# simduino.net
KiCad netlist of a schematic drawn in EAGLE
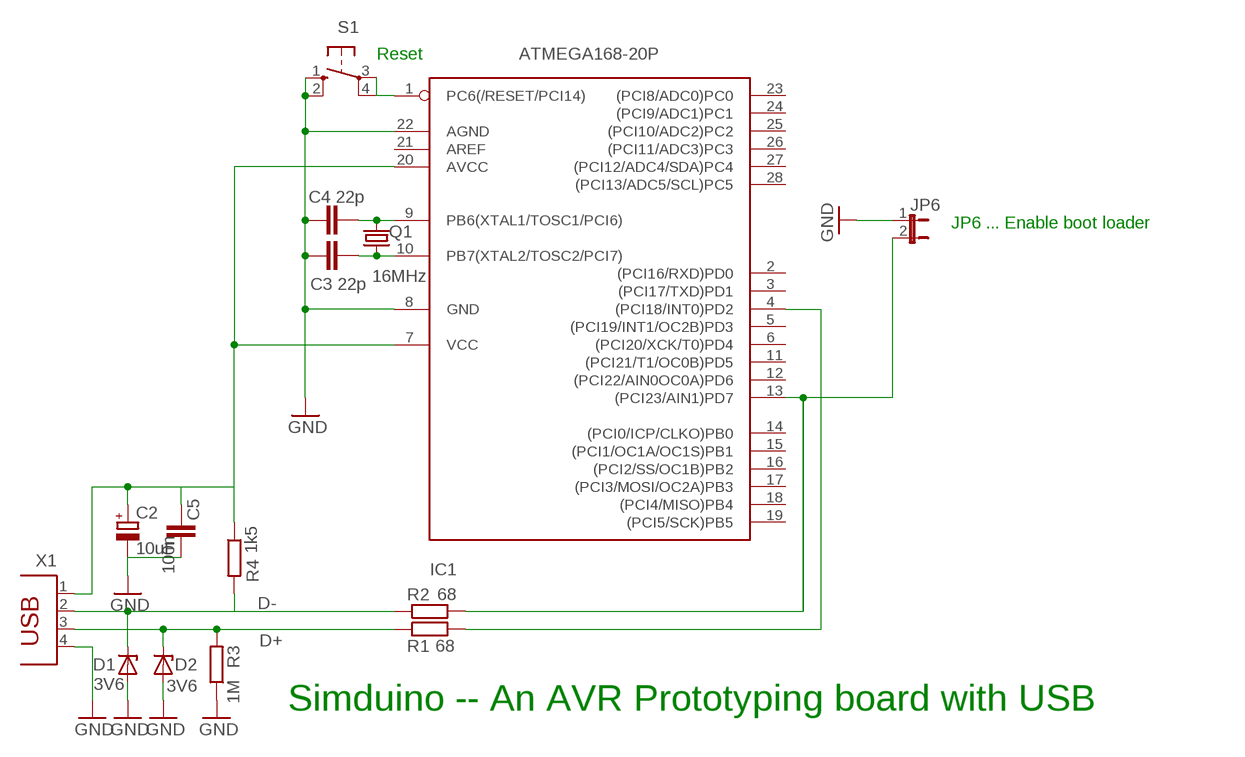
[diagram p0: schematic, sheet 1]

(export (version "E")
  (design (tool "Eeschema 10.0.6"))
  (components
    (comp (ref "C2")
      (value "10uF")
      (footprint "eagle-import:E2,5-6E")
      (libsource (lib "eagle-import") (part "CPOL-EUE2,5-6E"))
    )
    (comp (ref "C3")
      (value "22p")
      (footprint "eagle-import:C025-024X044")
      (libsource (lib "eagle-import") (part "C-EU025-024X044"))
    )
    (comp (ref "C4")
      (value "22p")
      (footprint "eagle-import:C025-024X044")
      (libsource (lib "eagle-import") (part "C-EU025-024X044"))
    )
    (comp (ref "C5")
      (value "100n")
      (footprint "eagle-import:C025_050-025X075")
      (libsource (lib "eagle-import") (part "C-EU025_050-025X075"))
    )
    (comp (ref "D1")
      (value "3V6")
      (footprint "eagle-import:DO34Z7")
      (libsource (lib "eagle-import") (part "ZENER-DIODEDO34-7"))
    )
    (comp (ref "D2")
      (value "3V6")
      (footprint "eagle-import:DO34Z7")
      (libsource (lib "eagle-import") (part "ZENER-DIODEDO34-7"))
    )
    (comp (ref "IC1")
      (value "ATMEGA168-20P")
      (footprint "eagle-import:DIL28-3")
      (libsource (lib "eagle-import") (part "ATMEGA168P-20"))
    )
    (comp (ref "JP6")
      (value "JP1E")
      (footprint "eagle-import:JP1")
      (libsource (lib "eagle-import") (part "JP1E"))
    )
    (comp (ref "Q1")
      (value "16MHz")
      (footprint "eagle-import:HC49_S")
      (libsource (lib "eagle-import") (part "CRYSTALHC49S"))
    )
    (comp (ref "R1")
      (value "68")
      (footprint "eagle-import:0207_10")
      (libsource (lib "eagle-import") (part "R-EU_0207/10"))
    )
    (comp (ref "R2")
      (value "68")
      (footprint "eagle-import:0207_10")
      (libsource (lib "eagle-import") (part "R-EU_0207/10"))
    )
    (comp (ref "R3")
      (value "1M")
      (footprint "eagle-import:0207_10")
      (libsource (lib "eagle-import") (part "R-EU_0207/10"))
    )
    (comp (ref "R4")
      (value "1k5")
      (footprint "eagle-import:0207_10")
      (libsource (lib "eagle-import") (part "R-EU_0207/10"))
    )
    (comp (ref "S1")
      (value "10-XX")
      (footprint "eagle-import:B3F-10XX")
      (libsource (lib "eagle-import") (part "10-XX"))
    )
    (comp (ref "X1")
      (value "PN61729")
      (footprint "eagle-import:PN61729")
      (libsource (lib "eagle-import") (part "PN61729"))
    )
  )
  (nets
    (net (code "1") (name "/D+") (class "Default")
      (node (ref "D2") (pin "C") (pinfunction "C_C") (pintype "passive"))
      (node (ref "R1") (pin "1") (pinfunction "1_1") (pintype "passive"))
      (node (ref "R3") (pin "2") (pinfunction "2_2") (pintype "passive"))
      (node (ref "X1") (pin "3") (pinfunction "3_3") (pintype "bidirectional"))
    )
    (net (code "2") (name "/D-") (class "Default")
      (node (ref "D1") (pin "C") (pinfunction "C_C") (pintype "passive"))
      (node (ref "R2") (pin "1") (pinfunction "1_1") (pintype "passive"))
      (node (ref "R4") (pin "2") (pinfunction "2_2") (pintype "passive"))
      (node (ref "X1") (pin "2") (pinfunction "2_2") (pintype "bidirectional"))
    )
    (net (code "3") (name "GND") (class "Default")
      (node (ref "C2") (pin "-") (pinfunction "-_-") (pintype "passive"))
      (node (ref "C3") (pin "1") (pinfunction "1_1") (pintype "passive"))
      (node (ref "C4") (pin "1") (pinfunction "1_1") (pintype "passive"))
      (node (ref "C5") (pin "2") (pinfunction "2_2") (pintype "passive"))
      (node (ref "D1") (pin "A") (pinfunction "A_A") (pintype "passive"))
      (node (ref "D2") (pin "A") (pinfunction "A_A") (pintype "passive"))
      (node (ref "IC1") (pin "22") (pinfunction "AGND_22") (pintype "bidirectional"))
      (node (ref "IC1") (pin "8") (pinfunction "GND_8") (pintype "bidirectional"))
      (node (ref "JP6") (pin "1") (pinfunction "1_1") (pintype "passive"))
      (node (ref "R3") (pin "1") (pinfunction "1_1") (pintype "passive"))
      (node (ref "S1") (pin "1") (pinfunction "S_1") (pintype "passive"))
      (node (ref "S1") (pin "2") (pinfunction "S1_2") (pintype "passive"))
      (node (ref "X1") (pin "4") (pinfunction "4_4") (pintype "bidirectional"))
    )
    (net (code "4") (name "Net-(IC1-(PCI18{slash}INT0)PD2)") (class "Default")
      (node (ref "IC1") (pin "4") (pinfunction "(PCI18/INT0)PD2_4") (pintype "bidirectional"))
      (node (ref "R1") (pin "2") (pinfunction "2_2") (pintype "passive"))
    )
    (net (code "5") (name "Net-(IC1-(PCI23{slash}AIN1)PD7)") (class "Default")
      (node (ref "IC1") (pin "13") (pinfunction "(PCI23/AIN1)PD7_13") (pintype "bidirectional"))
      (node (ref "JP6") (pin "2") (pinfunction "2_2") (pintype "passive"))
      (node (ref "R2") (pin "2") (pinfunction "2_2") (pintype "passive"))
    )
    (net (code "6") (name "Net-(IC1-AVCC)") (class "Default")
      (node (ref "C2") (pin "+") (pinfunction "+_+") (pintype "passive"))
      (node (ref "C5") (pin "1") (pinfunction "1_1") (pintype "passive"))
      (node (ref "IC1") (pin "20") (pinfunction "AVCC_20") (pintype "bidirectional"))
      (node (ref "IC1") (pin "7") (pinfunction "VCC_7") (pintype "bidirectional"))
      (node (ref "R4") (pin "1") (pinfunction "1_1") (pintype "passive"))
      (node (ref "X1") (pin "1") (pinfunction "1_1") (pintype "bidirectional"))
    )
    (net (code "7") (name "Net-(IC1-PB6(XTAL1{slash}TOSC1{slash}PCI6))") (class "Default")
      (node (ref "C4") (pin "2") (pinfunction "2_2") (pintype "passive"))
      (node (ref "IC1") (pin "9") (pinfunction "PB6(XTAL1/TOSC1/PCI6)_9") (pintype "bidirectional"))
      (node (ref "Q1") (pin "2") (pinfunction "2_2") (pintype "passive"))
    )
    (net (code "8") (name "Net-(IC1-PB7(XTAL2{slash}TOSC2{slash}PCI7))") (class "Default")
      (node (ref "C3") (pin "2") (pinfunction "2_2") (pintype "passive"))
      (node (ref "IC1") (pin "10") (pinfunction "PB7(XTAL2/TOSC2/PCI7)_10") (pintype "bidirectional"))
      (node (ref "Q1") (pin "1") (pinfunction "1_1") (pintype "passive"))
    )
    (net (code "9") (name "Net-(IC1-PC6({slash}RESET{slash}PCI14))") (class "Default")
      (node (ref "IC1") (pin "1") (pinfunction "PC6(/RESET/PCI14)_1") (pintype "bidirectional"))
      (node (ref "S1") (pin "3") (pinfunction "P_3") (pintype "passive"))
      (node (ref "S1") (pin "4") (pinfunction "P1_4") (pintype "passive"))
    )
    (net (code "10") (name "unconnected-(IC1-(PCI0{slash}ICP{slash}CLKO)PB0-Pad14)") (class "Default")
      (node (ref "IC1") (pin "14") (pinfunction "(PCI0/ICP/CLKO)PB0_14") (pintype "bidirectional"))
    )
    (net (code "11") (name "unconnected-(IC1-(PCI1{slash}OC1A{slash}OC1S)PB1-Pad15)") (class "Default")
      (node (ref "IC1") (pin "15") (pinfunction "(PCI1/OC1A/OC1S)PB1_15") (pintype "bidirectional"))
    )
    (net (code "12") (name "unconnected-(IC1-(PCI2{slash}SS{slash}OC1B)PB2-Pad16)") (class "Default")
      (node (ref "IC1") (pin "16") (pinfunction "(PCI2/SS/OC1B)PB2_16") (pintype "bidirectional"))
    )
    (net (code "13") (name "unconnected-(IC1-(PCI3{slash}MOSI{slash}OC2A)PB3-Pad17)") (class "Default")
      (node (ref "IC1") (pin "17") (pinfunction "(PCI3/MOSI/OC2A)PB3_17") (pintype "bidirectional"))
    )
    (net (code "14") (name "unconnected-(IC1-(PCI4{slash}MISO)PB4-Pad18)") (class "Default")
      (node (ref "IC1") (pin "18") (pinfunction "(PCI4/MISO)PB4_18") (pintype "bidirectional"))
    )
    (net (code "15") (name "unconnected-(IC1-(PCI5{slash}SCK)PB5-Pad19)") (class "Default")
      (node (ref "IC1") (pin "19") (pinfunction "(PCI5/SCK)PB5_19") (pintype "bidirectional"))
    )
    (net (code "16") (name "unconnected-(IC1-(PCI8{slash}ADC0)PC0-Pad23)") (class "Default")
      (node (ref "IC1") (pin "23") (pinfunction "(PCI8/ADC0)PC0_23") (pintype "bidirectional"))
    )
    (net (code "17") (name "unconnected-(IC1-(PCI9{slash}ADC1)PC1-Pad24)") (class "Default")
      (node (ref "IC1") (pin "24") (pinfunction "(PCI9/ADC1)PC1_24") (pintype "bidirectional"))
    )
    (net (code "18") (name "unconnected-(IC1-(PCI10{slash}ADC2)PC2-Pad25)") (class "Default")
      (node (ref "IC1") (pin "25") (pinfunction "(PCI10/ADC2)PC2_25") (pintype "bidirectional"))
    )
    (net (code "19") (name "unconnected-(IC1-(PCI11{slash}ADC3)PC3-Pad26)") (class "Default")
      (node (ref "IC1") (pin "26") (pinfunction "(PCI11/ADC3)PC3_26") (pintype "bidirectional"))
    )
    (net (code "20") (name "unconnected-(IC1-(PCI12{slash}ADC4{slash}SDA)PC4-Pad27)") (class "Default")
      (node (ref "IC1") (pin "27") (pinfunction "(PCI12/ADC4/SDA)PC4_27") (pintype "bidirectional"))
    )
    (net (code "21") (name "unconnected-(IC1-(PCI13{slash}ADC5{slash}SCL)PC5-Pad28)") (class "Default")
      (node (ref "IC1") (pin "28") (pinfunction "(PCI13/ADC5/SCL)PC5_28") (pintype "bidirectional"))
    )
    (net (code "22") (name "unconnected-(IC1-(PCI16{slash}RXD)PD0-Pad2)") (class "Default")
      (node (ref "IC1") (pin "2") (pinfunction "(PCI16/RXD)PD0_2") (pintype "bidirectional"))
    )
    (net (code "23") (name "unconnected-(IC1-(PCI17{slash}TXD)PD1-Pad3)") (class "Default")
      (node (ref "IC1") (pin "3") (pinfunction "(PCI17/TXD)PD1_3") (pintype "bidirectional"))
    )
    (net (code "24") (name "unconnected-(IC1-(PCI19{slash}INT1{slash}OC2B)PD3-Pad5)") (class "Default")
      (node (ref "IC1") (pin "5") (pinfunction "(PCI19/INT1/OC2B)PD3_5") (pintype "bidirectional"))
    )
    (net (code "25") (name "unconnected-(IC1-(PCI20{slash}XCK{slash}T0)PD4-Pad6)") (class "Default")
      (node (ref "IC1") (pin "6") (pinfunction "(PCI20/XCK/T0)PD4_6") (pintype "bidirectional"))
    )
    (net (code "26") (name "unconnected-(IC1-(PCI21{slash}T1{slash}OC0B)PD5-Pad11)") (class "Default")
      (node (ref "IC1") (pin "11") (pinfunction "(PCI21/T1/OC0B)PD5_11") (pintype "bidirectional"))
    )
    (net (code "27") (name "unconnected-(IC1-(PCI22{slash}AIN0OC0A)PD6-Pad12)") (class "Default")
      (node (ref "IC1") (pin "12") (pinfunction "(PCI22/AIN0OC0A)PD6_12") (pintype "bidirectional"))
    )
    (net (code "28") (name "unconnected-(IC1-AREF-Pad21)") (class "Default")
      (node (ref "IC1") (pin "21") (pinfunction "AREF_21") (pintype "bidirectional"))
    )
  )
)
